# node-test-array.net
KiCad netlist of a schematic drawn in Altium Designer
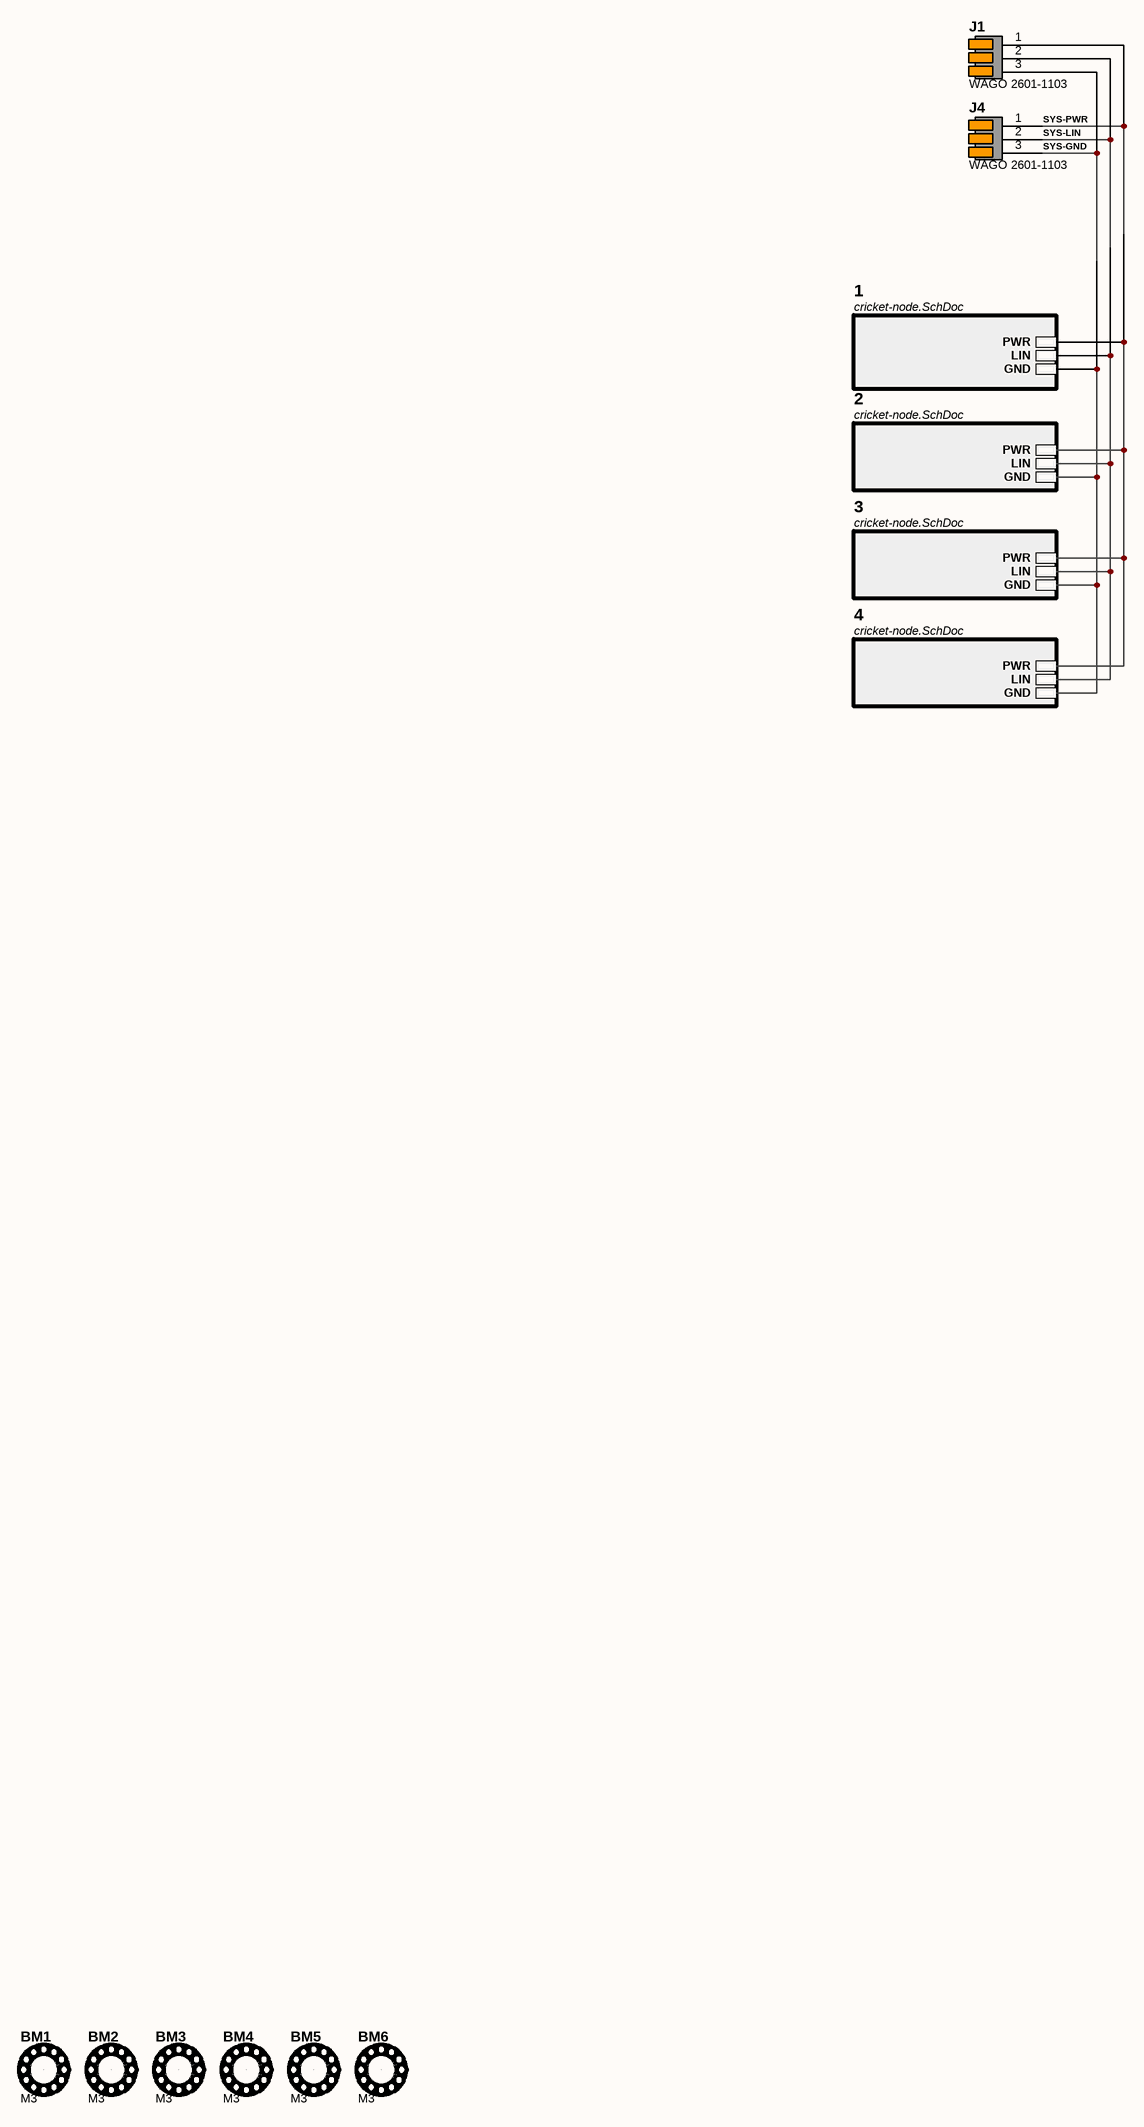
[diagram p0: node-test-array.SchDoc]

(export (version "E")
  (design (tool "Eeschema 10.0.6"))
  (components
    (comp (ref "BM1")
      (value "M3")
      (footprint "M3")
      (description "M3 screw hole ISO standard 3.6mm clearance 16 conductivity holes 6.3mm pad size")
      (fields (field (name "MANUFACTURER") "Wavenumber"))
      (libsource (lib "mechanical") (part "screw-hole"))
    )
    (comp (ref "BM2")
      (value "M3")
      (footprint "M3")
      (description "M3 screw hole ISO standard 3.6mm clearance 16 conductivity holes 6.3mm pad size")
      (fields (field (name "MANUFACTURER") "Wavenumber"))
      (libsource (lib "mechanical") (part "screw-hole"))
    )
    (comp (ref "BM3")
      (value "M3")
      (footprint "M3")
      (description "M3 screw hole ISO standard 3.6mm clearance 16 conductivity holes 6.3mm pad size")
      (fields (field (name "MANUFACTURER") "Wavenumber"))
      (libsource (lib "mechanical") (part "screw-hole"))
    )
    (comp (ref "BM4")
      (value "M3")
      (footprint "M3")
      (description "M3 screw hole ISO standard 3.6mm clearance 16 conductivity holes 6.3mm pad size")
      (fields (field (name "MANUFACTURER") "Wavenumber"))
      (libsource (lib "mechanical") (part "screw-hole"))
    )
    (comp (ref "BM5")
      (value "M3")
      (footprint "M3")
      (description "M3 screw hole ISO standard 3.6mm clearance 16 conductivity holes 6.3mm pad size")
      (fields (field (name "MANUFACTURER") "Wavenumber"))
      (libsource (lib "mechanical") (part "screw-hole"))
    )
    (comp (ref "BM6")
      (value "M3")
      (footprint "M3")
      (description "M3 screw hole ISO standard 3.6mm clearance 16 conductivity holes 6.3mm pad size")
      (fields (field (name "MANUFACTURER") "Wavenumber"))
      (libsource (lib "mechanical") (part "screw-hole"))
    )
    (comp (ref "J1")
      (value "WAGO 2601-1103")
      (footprint "2601-1103")
      (description "3 Position Wire to Board Terminal Block Horizontal with Board 0.137\" (3.50mm) Through Hole")
      (fields (field (name "INTERNAL PART NUMBER") "2601-1103") (field (name "MANUFACTURER") "Wago"))
      (libsource (lib "connector") (part "2601-1103"))
    )
    (comp (ref "J4")
      (value "WAGO 2601-1103")
      (footprint "2601-1103")
      (description "3 Position Wire to Board Terminal Block Horizontal with Board 0.137\" (3.50mm) Through Hole")
      (fields (field (name "INTERNAL PART NUMBER") "2601-1103") (field (name "MANUFACTURER") "Wago"))
      (libsource (lib "connector") (part "2601-1103"))
    )
  )
  (nets
    (net (code "1") (name "/SYS-GND") (class "Default")
      (node (ref "J1") (pin "3") (pinfunction "3_3") (pintype "passive"))
      (node (ref "J4") (pin "3") (pinfunction "3_3") (pintype "passive"))
    )
    (net (code "2") (name "/SYS-LIN") (class "Default")
      (node (ref "J1") (pin "2") (pinfunction "2_2") (pintype "passive"))
      (node (ref "J4") (pin "2") (pinfunction "2_2") (pintype "passive"))
    )
    (net (code "3") (name "/SYS-PWR") (class "Default")
      (node (ref "J1") (pin "1") (pinfunction "1_1") (pintype "passive"))
      (node (ref "J4") (pin "1") (pinfunction "1_1") (pintype "passive"))
    )
    (net (code "4") (name "unconnected-(BM1-Pad1)") (class "Default")
      (node (ref "BM1") (pin "1") (pinfunction "1_1") (pintype "passive"))
    )
    (net (code "5") (name "unconnected-(BM2-Pad1)") (class "Default")
      (node (ref "BM2") (pin "1") (pinfunction "1_1") (pintype "passive"))
    )
    (net (code "6") (name "unconnected-(BM3-Pad1)") (class "Default")
      (node (ref "BM3") (pin "1") (pinfunction "1_1") (pintype "passive"))
    )
    (net (code "7") (name "unconnected-(BM4-Pad1)") (class "Default")
      (node (ref "BM4") (pin "1") (pinfunction "1_1") (pintype "passive"))
    )
    (net (code "8") (name "unconnected-(BM5-Pad1)") (class "Default")
      (node (ref "BM5") (pin "1") (pinfunction "1_1") (pintype "passive"))
    )
    (net (code "9") (name "unconnected-(BM6-Pad1)") (class "Default")
      (node (ref "BM6") (pin "1") (pinfunction "1_1") (pintype "passive"))
    )
  )
)
